# Keyboard40.net
KiCad netlist of a schematic drawn in EAGLE
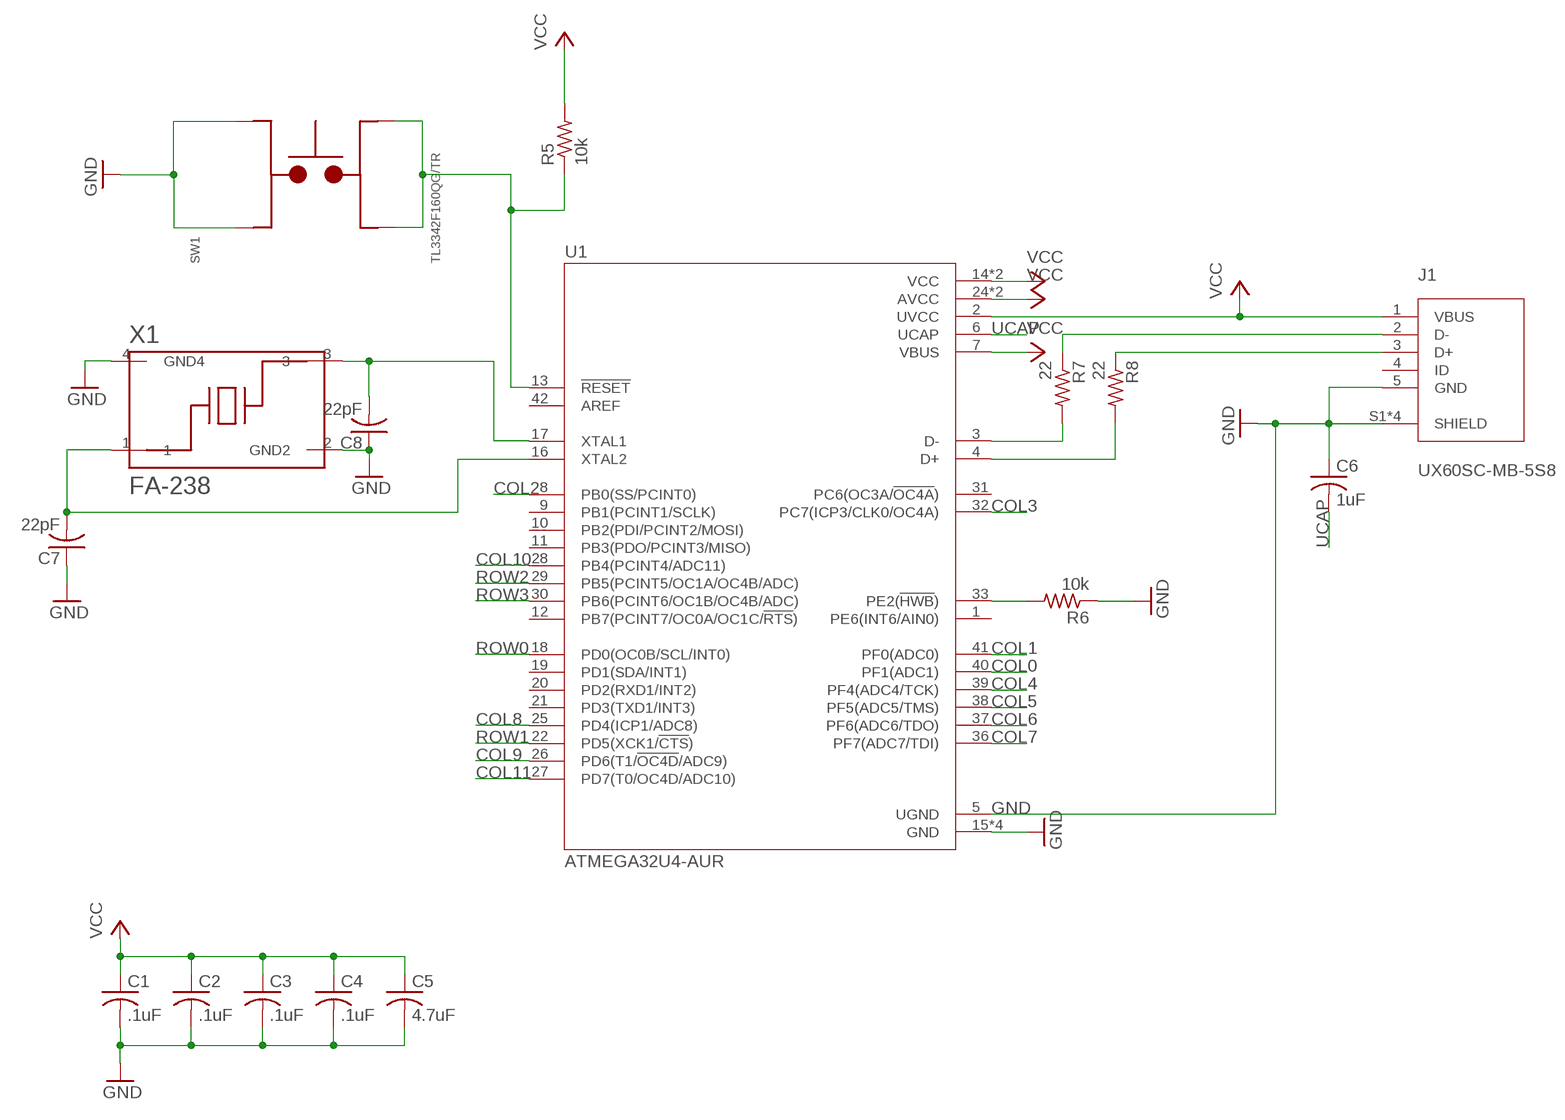
[diagram p0: schematic, sheet 1]
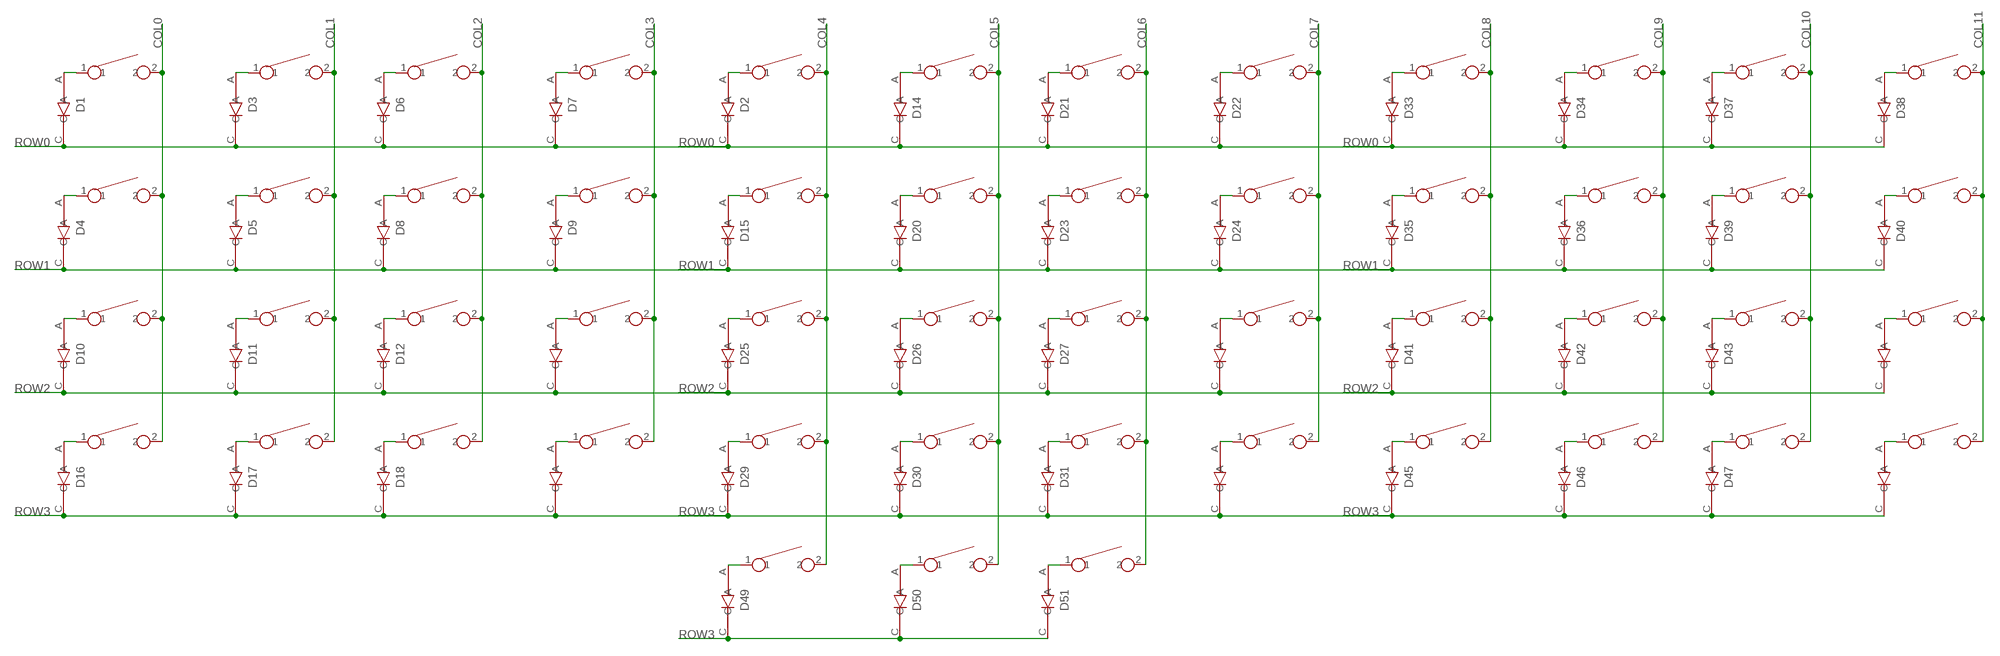
[diagram p1: schematic, sheet 2]

(export (version "E")
  (design (tool "Eeschema 10.0.6"))
  (components
    (comp (ref "D1")
      (value "BAV21W-7-F")
      (footprint "eagle-import:SOD3715X135N")
      (fields (field (name "DIGI-KEY_PART_NUMBER") "BAV21W-FDICT-ND") (field (name "MF") "Diodes Inc."))
      (libsource (lib "eagle-import") (part "BAV21W-7-F"))
    )
    (comp (ref "D2")
      (value "BAV21W-7-F")
      (footprint "eagle-import:SOD3715X135N")
      (fields (field (name "DIGI-KEY_PART_NUMBER") "BAV21W-FDICT-ND") (field (name "MF") "Diodes Inc."))
      (libsource (lib "eagle-import") (part "BAV21W-7-F"))
    )
    (comp (ref "D3")
      (value "BAV21W-7-F")
      (footprint "eagle-import:SOD3715X135N")
      (fields (field (name "DIGI-KEY_PART_NUMBER") "BAV21W-FDICT-ND") (field (name "MF") "Diodes Inc."))
      (libsource (lib "eagle-import") (part "BAV21W-7-F"))
    )
    (comp (ref "D4")
      (value "BAV21W-7-F")
      (footprint "eagle-import:SOD3715X135N")
      (fields (field (name "DIGI-KEY_PART_NUMBER") "BAV21W-FDICT-ND") (field (name "MF") "Diodes Inc."))
      (libsource (lib "eagle-import") (part "BAV21W-7-F"))
    )
    (comp (ref "D5")
      (value "BAV21W-7-F")
      (footprint "eagle-import:SOD3715X135N")
      (fields (field (name "DIGI-KEY_PART_NUMBER") "BAV21W-FDICT-ND") (field (name "MF") "Diodes Inc."))
      (libsource (lib "eagle-import") (part "BAV21W-7-F"))
    )
    (comp (ref "D6")
      (value "BAV21W-7-F")
      (footprint "eagle-import:SOD3715X135N")
      (fields (field (name "DIGI-KEY_PART_NUMBER") "BAV21W-FDICT-ND") (field (name "MF") "Diodes Inc."))
      (libsource (lib "eagle-import") (part "BAV21W-7-F"))
    )
    (comp (ref "D7")
      (value "BAV21W-7-F")
      (footprint "eagle-import:SOD3715X135N")
      (fields (field (name "DIGI-KEY_PART_NUMBER") "BAV21W-FDICT-ND") (field (name "MF") "Diodes Inc."))
      (libsource (lib "eagle-import") (part "BAV21W-7-F"))
    )
    (comp (ref "D8")
      (value "BAV21W-7-F")
      (footprint "eagle-import:SOD3715X135N")
      (fields (field (name "DIGI-KEY_PART_NUMBER") "BAV21W-FDICT-ND") (field (name "MF") "Diodes Inc."))
      (libsource (lib "eagle-import") (part "BAV21W-7-F"))
    )
    (comp (ref "D9")
      (value "BAV21W-7-F")
      (footprint "eagle-import:SOD3715X135N")
      (fields (field (name "DIGI-KEY_PART_NUMBER") "BAV21W-FDICT-ND") (field (name "MF") "Diodes Inc."))
      (libsource (lib "eagle-import") (part "BAV21W-7-F"))
    )
    (comp (ref "D10")
      (value "BAV21W-7-F")
      (footprint "eagle-import:SOD3715X135N")
      (fields (field (name "DIGI-KEY_PART_NUMBER") "BAV21W-FDICT-ND") (field (name "MF") "Diodes Inc."))
      (libsource (lib "eagle-import") (part "BAV21W-7-F"))
    )
    (comp (ref "D11")
      (value "BAV21W-7-F")
      (footprint "eagle-import:SOD3715X135N")
      (fields (field (name "DIGI-KEY_PART_NUMBER") "BAV21W-FDICT-ND") (field (name "MF") "Diodes Inc."))
      (libsource (lib "eagle-import") (part "BAV21W-7-F"))
    )
    (comp (ref "D12")
      (value "BAV21W-7-F")
      (footprint "eagle-import:SOD3715X135N")
      (fields (field (name "DIGI-KEY_PART_NUMBER") "BAV21W-FDICT-ND") (field (name "MF") "Diodes Inc."))
      (libsource (lib "eagle-import") (part "BAV21W-7-F"))
    )
    (comp (ref "D13")
      (value "BAV21W-7-F")
      (footprint "eagle-import:SOD3715X135N")
      (fields (field (name "DIGI-KEY_PART_NUMBER") "BAV21W-FDICT-ND") (field (name "MF") "Diodes Inc."))
      (libsource (lib "eagle-import") (part "BAV21W-7-F"))
    )
    (comp (ref "D14")
      (value "BAV21W-7-F")
      (footprint "eagle-import:SOD3715X135N")
      (fields (field (name "DIGI-KEY_PART_NUMBER") "BAV21W-FDICT-ND") (field (name "MF") "Diodes Inc."))
      (libsource (lib "eagle-import") (part "BAV21W-7-F"))
    )
    (comp (ref "D15")
      (value "BAV21W-7-F")
      (footprint "eagle-import:SOD3715X135N")
      (fields (field (name "DIGI-KEY_PART_NUMBER") "BAV21W-FDICT-ND") (field (name "MF") "Diodes Inc."))
      (libsource (lib "eagle-import") (part "BAV21W-7-F"))
    )
    (comp (ref "D16")
      (value "BAV21W-7-F")
      (footprint "eagle-import:SOD3715X135N")
      (fields (field (name "DIGI-KEY_PART_NUMBER") "BAV21W-FDICT-ND") (field (name "MF") "Diodes Inc."))
      (libsource (lib "eagle-import") (part "BAV21W-7-F"))
    )
    (comp (ref "D17")
      (value "BAV21W-7-F")
      (footprint "eagle-import:SOD3715X135N")
      (fields (field (name "DIGI-KEY_PART_NUMBER") "BAV21W-FDICT-ND") (field (name "MF") "Diodes Inc."))
      (libsource (lib "eagle-import") (part "BAV21W-7-F"))
    )
    (comp (ref "D18")
      (value "BAV21W-7-F")
      (footprint "eagle-import:SOD3715X135N")
      (fields (field (name "DIGI-KEY_PART_NUMBER") "BAV21W-FDICT-ND") (field (name "MF") "Diodes Inc."))
      (libsource (lib "eagle-import") (part "BAV21W-7-F"))
    )
    (comp (ref "D19")
      (value "BAV21W-7-F")
      (footprint "eagle-import:SOD3715X135N")
      (fields (field (name "DIGI-KEY_PART_NUMBER") "BAV21W-FDICT-ND") (field (name "MF") "Diodes Inc."))
      (libsource (lib "eagle-import") (part "BAV21W-7-F"))
    )
    (comp (ref "D20")
      (value "BAV21W-7-F")
      (footprint "eagle-import:SOD3715X135N")
      (fields (field (name "DIGI-KEY_PART_NUMBER") "BAV21W-FDICT-ND") (field (name "MF") "Diodes Inc."))
      (libsource (lib "eagle-import") (part "BAV21W-7-F"))
    )
    (comp (ref "D21")
      (value "BAV21W-7-F")
      (footprint "eagle-import:SOD3715X135N")
      (fields (field (name "DIGI-KEY_PART_NUMBER") "BAV21W-FDICT-ND") (field (name "MF") "Diodes Inc."))
      (libsource (lib "eagle-import") (part "BAV21W-7-F"))
    )
    (comp (ref "D22")
      (value "BAV21W-7-F")
      (footprint "eagle-import:SOD3715X135N")
      (fields (field (name "DIGI-KEY_PART_NUMBER") "BAV21W-FDICT-ND") (field (name "MF") "Diodes Inc."))
      (libsource (lib "eagle-import") (part "BAV21W-7-F"))
    )
    (comp (ref "D23")
      (value "BAV21W-7-F")
      (footprint "eagle-import:SOD3715X135N")
      (fields (field (name "DIGI-KEY_PART_NUMBER") "BAV21W-FDICT-ND") (field (name "MF") "Diodes Inc."))
      (libsource (lib "eagle-import") (part "BAV21W-7-F"))
    )
    (comp (ref "D24")
      (value "BAV21W-7-F")
      (footprint "eagle-import:SOD3715X135N")
      (fields (field (name "DIGI-KEY_PART_NUMBER") "BAV21W-FDICT-ND") (field (name "MF") "Diodes Inc."))
      (libsource (lib "eagle-import") (part "BAV21W-7-F"))
    )
    (comp (ref "D25")
      (value "BAV21W-7-F")
      (footprint "eagle-import:SOD3715X135N")
      (fields (field (name "DIGI-KEY_PART_NUMBER") "BAV21W-FDICT-ND") (field (name "MF") "Diodes Inc."))
      (libsource (lib "eagle-import") (part "BAV21W-7-F"))
    )
    (comp (ref "D26")
      (value "BAV21W-7-F")
      (footprint "eagle-import:SOD3715X135N")
      (fields (field (name "DIGI-KEY_PART_NUMBER") "BAV21W-FDICT-ND") (field (name "MF") "Diodes Inc."))
      (libsource (lib "eagle-import") (part "BAV21W-7-F"))
    )
    (comp (ref "D27")
      (value "BAV21W-7-F")
      (footprint "eagle-import:SOD3715X135N")
      (fields (field (name "DIGI-KEY_PART_NUMBER") "BAV21W-FDICT-ND") (field (name "MF") "Diodes Inc."))
      (libsource (lib "eagle-import") (part "BAV21W-7-F"))
    )
    (comp (ref "D28")
      (value "BAV21W-7-F")
      (footprint "eagle-import:SOD3715X135N")
      (fields (field (name "DIGI-KEY_PART_NUMBER") "BAV21W-FDICT-ND") (field (name "MF") "Diodes Inc."))
      (libsource (lib "eagle-import") (part "BAV21W-7-F"))
    )
    (comp (ref "D29")
      (value "BAV21W-7-F")
      (footprint "eagle-import:SOD3715X135N")
      (fields (field (name "DIGI-KEY_PART_NUMBER") "BAV21W-FDICT-ND") (field (name "MF") "Diodes Inc."))
      (libsource (lib "eagle-import") (part "BAV21W-7-F"))
    )
    (comp (ref "D30")
      (value "BAV21W-7-F")
      (footprint "eagle-import:SOD3715X135N")
      (fields (field (name "DIGI-KEY_PART_NUMBER") "BAV21W-FDICT-ND") (field (name "MF") "Diodes Inc."))
      (libsource (lib "eagle-import") (part "BAV21W-7-F"))
    )
    (comp (ref "D31")
      (value "BAV21W-7-F")
      (footprint "eagle-import:SOD3715X135N")
      (fields (field (name "DIGI-KEY_PART_NUMBER") "BAV21W-FDICT-ND") (field (name "MF") "Diodes Inc."))
      (libsource (lib "eagle-import") (part "BAV21W-7-F"))
    )
    (comp (ref "D32")
      (value "BAV21W-7-F")
      (footprint "eagle-import:SOD3715X135N")
      (fields (field (name "DIGI-KEY_PART_NUMBER") "BAV21W-FDICT-ND") (field (name "MF") "Diodes Inc."))
      (libsource (lib "eagle-import") (part "BAV21W-7-F"))
    )
    (comp (ref "D33")
      (value "BAV21W-7-F")
      (footprint "eagle-import:SOD3715X135N")
      (fields (field (name "DIGI-KEY_PART_NUMBER") "BAV21W-FDICT-ND") (field (name "MF") "Diodes Inc."))
      (libsource (lib "eagle-import") (part "BAV21W-7-F"))
    )
    (comp (ref "D34")
      (value "BAV21W-7-F")
      (footprint "eagle-import:SOD3715X135N")
      (fields (field (name "DIGI-KEY_PART_NUMBER") "BAV21W-FDICT-ND") (field (name "MF") "Diodes Inc."))
      (libsource (lib "eagle-import") (part "BAV21W-7-F"))
    )
    (comp (ref "D35")
      (value "BAV21W-7-F")
      (footprint "eagle-import:SOD3715X135N")
      (fields (field (name "DIGI-KEY_PART_NUMBER") "BAV21W-FDICT-ND") (field (name "MF") "Diodes Inc."))
      (libsource (lib "eagle-import") (part "BAV21W-7-F"))
    )
    (comp (ref "D36")
      (value "BAV21W-7-F")
      (footprint "eagle-import:SOD3715X135N")
      (fields (field (name "DIGI-KEY_PART_NUMBER") "BAV21W-FDICT-ND") (field (name "MF") "Diodes Inc."))
      (libsource (lib "eagle-import") (part "BAV21W-7-F"))
    )
    (comp (ref "D37")
      (value "BAV21W-7-F")
      (footprint "eagle-import:SOD3715X135N")
      (fields (field (name "DIGI-KEY_PART_NUMBER") "BAV21W-FDICT-ND") (field (name "MF") "Diodes Inc."))
      (libsource (lib "eagle-import") (part "BAV21W-7-F"))
    )
    (comp (ref "D38")
      (value "BAV21W-7-F")
      (footprint "eagle-import:SOD3715X135N")
      (fields (field (name "DIGI-KEY_PART_NUMBER") "BAV21W-FDICT-ND") (field (name "MF") "Diodes Inc."))
      (libsource (lib "eagle-import") (part "BAV21W-7-F"))
    )
    (comp (ref "D39")
      (value "BAV21W-7-F")
      (footprint "eagle-import:SOD3715X135N")
      (fields (field (name "DIGI-KEY_PART_NUMBER") "BAV21W-FDICT-ND") (field (name "MF") "Diodes Inc."))
      (libsource (lib "eagle-import") (part "BAV21W-7-F"))
    )
    (comp (ref "D40")
      (value "BAV21W-7-F")
      (footprint "eagle-import:SOD3715X135N")
      (fields (field (name "DIGI-KEY_PART_NUMBER") "BAV21W-FDICT-ND") (field (name "MF") "Diodes Inc."))
      (libsource (lib "eagle-import") (part "BAV21W-7-F"))
    )
    (comp (ref "D41")
      (value "BAV21W-7-F")
      (footprint "eagle-import:SOD3715X135N")
      (fields (field (name "DIGI-KEY_PART_NUMBER") "BAV21W-FDICT-ND") (field (name "MF") "Diodes Inc."))
      (libsource (lib "eagle-import") (part "BAV21W-7-F"))
    )
    (comp (ref "D42")
      (value "BAV21W-7-F")
      (footprint "eagle-import:SOD3715X135N")
      (fields (field (name "DIGI-KEY_PART_NUMBER") "BAV21W-FDICT-ND") (field (name "MF") "Diodes Inc."))
      (libsource (lib "eagle-import") (part "BAV21W-7-F"))
    )
    (comp (ref "D43")
      (value "BAV21W-7-F")
      (footprint "eagle-import:SOD3715X135N")
      (fields (field (name "DIGI-KEY_PART_NUMBER") "BAV21W-FDICT-ND") (field (name "MF") "Diodes Inc."))
      (libsource (lib "eagle-import") (part "BAV21W-7-F"))
    )
    (comp (ref "D44")
      (value "BAV21W-7-F")
      (footprint "eagle-import:SOD3715X135N")
      (fields (field (name "DIGI-KEY_PART_NUMBER") "BAV21W-FDICT-ND") (field (name "MF") "Diodes Inc."))
      (libsource (lib "eagle-import") (part "BAV21W-7-F"))
    )
    (comp (ref "D45")
      (value "BAV21W-7-F")
      (footprint "eagle-import:SOD3715X135N")
      (fields (field (name "DIGI-KEY_PART_NUMBER") "BAV21W-FDICT-ND") (field (name "MF") "Diodes Inc."))
      (libsource (lib "eagle-import") (part "BAV21W-7-F"))
    )
    (comp (ref "D46")
      (value "BAV21W-7-F")
      (footprint "eagle-import:SOD3715X135N")
      (fields (field (name "DIGI-KEY_PART_NUMBER") "BAV21W-FDICT-ND") (field (name "MF") "Diodes Inc."))
      (libsource (lib "eagle-import") (part "BAV21W-7-F"))
    )
    (comp (ref "D47")
      (value "BAV21W-7-F")
      (footprint "eagle-import:SOD3715X135N")
      (fields (field (name "DIGI-KEY_PART_NUMBER") "BAV21W-FDICT-ND") (field (name "MF") "Diodes Inc."))
      (libsource (lib "eagle-import") (part "BAV21W-7-F"))
    )
    (comp (ref "D48")
      (value "BAV21W-7-F")
      (footprint "eagle-import:SOD3715X135N")
      (fields (field (name "DIGI-KEY_PART_NUMBER") "BAV21W-FDICT-ND") (field (name "MF") "Diodes Inc."))
      (libsource (lib "eagle-import") (part "BAV21W-7-F"))
    )
    (comp (ref "D49")
      (value "BAV21W-7-F")
      (footprint "eagle-import:SOD3715X135N")
      (fields (field (name "DIGI-KEY_PART_NUMBER") "BAV21W-FDICT-ND") (field (name "MF") "Diodes Inc."))
      (libsource (lib "eagle-import") (part "BAV21W-7-F"))
    )
    (comp (ref "D50")
      (value "BAV21W-7-F")
      (footprint "eagle-import:SOD3715X135N")
      (fields (field (name "DIGI-KEY_PART_NUMBER") "BAV21W-FDICT-ND") (field (name "MF") "Diodes Inc."))
      (libsource (lib "eagle-import") (part "BAV21W-7-F"))
    )
    (comp (ref "D51")
      (value "BAV21W-7-F")
      (footprint "eagle-import:SOD3715X135N")
      (fields (field (name "DIGI-KEY_PART_NUMBER") "BAV21W-FDICT-ND") (field (name "MF") "Diodes Inc."))
      (libsource (lib "eagle-import") (part "BAV21W-7-F"))
    )
    (comp (ref "U$1")
      (value "CHERRY_MXCHERRY_MX_PLATE")
      (footprint "eagle-import:CHERRY_MX_PLATE")
      (libsource (lib "eagle-import") (part "CHERRY_MXCHERRY_MX_PLATE"))
    )
    (comp (ref "U$2")
      (value "CHERRY_MXCHERRY_MX_PLATE")
      (footprint "eagle-import:CHERRY_MX_PLATE")
      (libsource (lib "eagle-import") (part "CHERRY_MXCHERRY_MX_PLATE"))
    )
    (comp (ref "U$3")
      (value "CHERRY_MXCHERRY_MX_PLATE")
      (footprint "eagle-import:CHERRY_MX_PLATE")
      (libsource (lib "eagle-import") (part "CHERRY_MXCHERRY_MX_PLATE"))
    )
    (comp (ref "U$4")
      (value "CHERRY_MXCHERRY_MX_PLATE")
      (footprint "eagle-import:CHERRY_MX_PLATE")
      (libsource (lib "eagle-import") (part "CHERRY_MXCHERRY_MX_PLATE"))
    )
    (comp (ref "U$5")
      (value "CHERRY_MXCHERRY_MX_PLATE")
      (footprint "eagle-import:CHERRY_MX_PLATE")
      (libsource (lib "eagle-import") (part "CHERRY_MXCHERRY_MX_PLATE"))
    )
    (comp (ref "U$6")
      (value "CHERRY_MXCHERRY_MX_PLATE")
      (footprint "eagle-import:CHERRY_MX_PLATE")
      (libsource (lib "eagle-import") (part "CHERRY_MXCHERRY_MX_PLATE"))
    )
    (comp (ref "U$7")
      (value "CHERRY_MXCHERRY_MX_PLATE")
      (footprint "eagle-import:CHERRY_MX_PLATE")
      (libsource (lib "eagle-import") (part "CHERRY_MXCHERRY_MX_PLATE"))
    )
    (comp (ref "U$8")
      (value "CHERRY_MXCHERRY_MX_PLATE")
      (footprint "eagle-import:CHERRY_MX_PLATE")
      (libsource (lib "eagle-import") (part "CHERRY_MXCHERRY_MX_PLATE"))
    )
    (comp (ref "U$9")
      (value "CHERRY_MXCHERRY_MX_PLATE")
      (footprint "eagle-import:CHERRY_MX_PLATE")
      (libsource (lib "eagle-import") (part "CHERRY_MXCHERRY_MX_PLATE"))
    )
    (comp (ref "U$10")
      (value "CHERRY_MXCHERRY_MX_PLATE")
      (footprint "eagle-import:CHERRY_MX_PLATE")
      (libsource (lib "eagle-import") (part "CHERRY_MXCHERRY_MX_PLATE"))
    )
    (comp (ref "U$11")
      (value "CHERRY_MXCHERRY_MX_PLATE")
      (footprint "eagle-import:CHERRY_MX_PLATE")
      (libsource (lib "eagle-import") (part "CHERRY_MXCHERRY_MX_PLATE"))
    )
    (comp (ref "U$12")
      (value "CHERRY_MXCHERRY_MX_PLATE")
      (footprint "eagle-import:CHERRY_MX_PLATE")
      (libsource (lib "eagle-import") (part "CHERRY_MXCHERRY_MX_PLATE"))
    )
    (comp (ref "U$13")
      (value "CHERRY_MXCHERRY_MX_1_2_PLATE")
      (footprint "eagle-import:CHERRY_MX_1_2_PLATE")
      (libsource (lib "eagle-import") (part "CHERRY_MXCHERRY_MX_1_2_PLATE"))
    )
    (comp (ref "U$14")
      (value "CHERRY_MXCHERRY_MX_1_2_PLATE")
      (footprint "eagle-import:CHERRY_MX_1_2_PLATE")
      (libsource (lib "eagle-import") (part "CHERRY_MXCHERRY_MX_1_2_PLATE"))
    )
    (comp (ref "U$15")
      (value "CHERRY_MXCHERRY_MX_1_2_PLATE")
      (footprint "eagle-import:CHERRY_MX_1_2_PLATE")
      (libsource (lib "eagle-import") (part "CHERRY_MXCHERRY_MX_1_2_PLATE"))
    )
    (comp (ref "U$16")
      (value "CHERRY_MXCHERRY_MX_PLATE")
      (footprint "eagle-import:CHERRY_MX_PLATE")
      (libsource (lib "eagle-import") (part "CHERRY_MXCHERRY_MX_PLATE"))
    )
    (comp (ref "U$17")
      (value "CHERRY_MXCHERRY_MX_PLATE")
      (footprint "eagle-import:CHERRY_MX_PLATE")
      (libsource (lib "eagle-import") (part "CHERRY_MXCHERRY_MX_PLATE"))
    )
    (comp (ref "U$18")
      (value "CHERRY_MXCHERRY_MX_PLATE")
      (footprint "eagle-import:CHERRY_MX_PLATE")
      (libsource (lib "eagle-import") (part "CHERRY_MXCHERRY_MX_PLATE"))
    )
    (comp (ref "U$19")
      (value "CHERRY_MXCHERRY_MX_PLATE")
      (footprint "eagle-import:CHERRY_MX_PLATE")
      (libsource (lib "eagle-import") (part "CHERRY_MXCHERRY_MX_PLATE"))
    )
    (comp (ref "U$20")
      (value "CHERRY_MXCHERRY_MX_PLATE")
      (footprint "eagle-import:CHERRY_MX_PLATE")
      (libsource (lib "eagle-import") (part "CHERRY_MXCHERRY_MX_PLATE"))
    )
    (comp (ref "U$21")
      (value "CHERRY_MXCHERRY_MX_PLATE")
      (footprint "eagle-import:CHERRY_MX_PLATE")
      (libsource (lib "eagle-import") (part "CHERRY_MXCHERRY_MX_PLATE"))
    )
    (comp (ref "U$22")
      (value "CHERRY_MXCHERRY_MX_PLATE")
      (footprint "eagle-import:CHERRY_MX_PLATE")
      (libsource (lib "eagle-import") (part "CHERRY_MXCHERRY_MX_PLATE"))
    )
    (comp (ref "U$23")
      (value "CHERRY_MXCHERRY_MX_PLATE")
      (footprint "eagle-import:CHERRY_MX_PLATE")
      (libsource (lib "eagle-import") (part "CHERRY_MXCHERRY_MX_PLATE"))
    )
    (comp (ref "U$24")
      (value "CHERRY_MXCHERRY_MX_PLATE")
      (footprint "eagle-import:CHERRY_MX_PLATE")
      (libsource (lib "eagle-import") (part "CHERRY_MXCHERRY_MX_PLATE"))
    )
    (comp (ref "U$25")
      (value "CHERRY_MXCHERRY_MX_PLATE")
      (footprint "eagle-import:CHERRY_MX_PLATE")
      (libsource (lib "eagle-import") (part "CHERRY_MXCHERRY_MX_PLATE"))
    )
    (comp (ref "U$26")
      (value "CHERRY_MXCHERRY_MX_PLATE")
      (footprint "eagle-import:CHERRY_MX_PLATE")
      (libsource (lib "eagle-import") (part "CHERRY_MXCHERRY_MX_PLATE"))
    )
    (comp (ref "U$27")
      (value "CHERRY_MXCHERRY_MX_PLATE")
      (footprint "eagle-import:CHERRY_MX_PLATE")
      (libsource (lib "eagle-import") (part "CHERRY_MXCHERRY_MX_PLATE"))
    )
    (comp (ref "U$28")
      (value "CHERRY_MXCHERRY_MX_PLATE")
      (footprint "eagle-import:CHERRY_MX_PLATE")
      (libsource (lib "eagle-import") (part "CHERRY_MXCHERRY_MX_PLATE"))
    )
    (comp (ref "U$29")
      (value "CHERRY_MXCHERRY_MX_PLATE")
      (footprint "eagle-import:CHERRY_MX_PLATE")
      (libsource (lib "eagle-import") (part "CHERRY_MXCHERRY_MX_PLATE"))
    )
    (comp (ref "U$30")
      (value "CHERRY_MXCHERRY_MX_PLATE")
      (footprint "eagle-import:CHERRY_MX_PLATE")
      (libsource (lib "eagle-import") (part "CHERRY_MXCHERRY_MX_PLATE"))
    )
    (comp (ref "U$31")
      (value "CHERRY_MXCHERRY_MX_PLATE")
      (footprint "eagle-import:CHERRY_MX_PLATE")
      (libsource (lib "eagle-import") (part "CHERRY_MXCHERRY_MX_PLATE"))
    )
    (comp (ref "U$32")
      (value "CHERRY_MXCHERRY_MX_PLATE")
      (footprint "eagle-import:CHERRY_MX_PLATE")
      (libsource (lib "eagle-import") (part "CHERRY_MXCHERRY_MX_PLATE"))
    )
    (comp (ref "U$33")
      (value "CHERRY_MXCHERRY_MX_PLATE")
      (footprint "eagle-import:CHERRY_MX_PLATE")
      (libsource (lib "eagle-import") (part "CHERRY_MXCHERRY_MX_PLATE"))
    )
    (comp (ref "U$34")
      (value "CHERRY_MXCHERRY_MX_PLATE")
      (footprint "eagle-import:CHERRY_MX_PLATE")
      (libsource (lib "eagle-import") (part "CHERRY_MXCHERRY_MX_PLATE"))
    )
    (comp (ref "U$35")
      (value "CHERRY_MXCHERRY_MX_PLATE")
      (footprint "eagle-import:CHERRY_MX_PLATE")
      (libsource (lib "eagle-import") (part "CHERRY_MXCHERRY_MX_PLATE"))
    )
    (comp (ref "U$36")
      (value "CHERRY_MXCHERRY_MX_PLATE")
      (footprint "eagle-import:CHERRY_MX_PLATE")
      (libsource (lib "eagle-import") (part "CHERRY_MXCHERRY_MX_PLATE"))
    )
    (comp (ref "U$37")
      (value "CHERRY_MXCHERRY_MX_PLATE")
      (footprint "eagle-import:CHERRY_MX_PLATE")
      (libsource (lib "eagle-import") (part "CHERRY_MXCHERRY_MX_PLATE"))
    )
    (comp (ref "U$38")
      (value "CHERRY_MXCHERRY_MX_PLATE")
      (footprint "eagle-import:CHERRY_MX_PLATE")
      (libsource (lib "eagle-import") (part "CHERRY_MXCHERRY_MX_PLATE"))
    )
    (comp (ref "U$39")
      (value "CHERRY_MXCHERRY_MX_PLATE")
      (footprint "eagle-import:CHERRY_MX_PLATE")
      (libsource (lib "eagle-import") (part "CHERRY_MXCHERRY_MX_PLATE"))
    )
    (comp (ref "U$40")
      (value "CHERRY_MXCHERRY_MX_PLATE")
      (footprint "eagle-import:CHERRY_MX_PLATE")
      (libsource (lib "eagle-import") (part "CHERRY_MXCHERRY_MX_PLATE"))
    )
    (comp (ref "U$41")
      (value "CHERRY_MXCHERRY_MX_PLATE")
      (footprint "eagle-import:CHERRY_MX_PLATE")
      (libsource (lib "eagle-import") (part "CHERRY_MXCHERRY_MX_PLATE"))
    )
    (comp (ref "U$42")
      (value "CHERRY_MXCHERRY_MX_PLATE")
      (footprint "eagle-import:CHERRY_MX_PLATE")
      (libsource (lib "eagle-import") (part "CHERRY_MXCHERRY_MX_PLATE"))
    )
    (comp (ref "U$43")
      (value "CHERRY_MXCHERRY_MX_PLATE")
      (footprint "eagle-import:CHERRY_MX_PLATE")
      (libsource (lib "eagle-import") (part "CHERRY_MXCHERRY_MX_PLATE"))
    )
    (comp (ref "U$44")
      (value "CHERRY_MXCHERRY_MX_PLATE")
      (footprint "eagle-import:CHERRY_MX_PLATE")
      (libsource (lib "eagle-import") (part "CHERRY_MXCHERRY_MX_PLATE"))
    )
    (comp (ref "U$45")
      (value "CHERRY_MXCHERRY_MX_PLATE")
      (footprint "eagle-import:CHERRY_MX_PLATE")
      (libsource (lib "eagle-import") (part "CHERRY_MXCHERRY_MX_PLATE"))
    )
    (comp (ref "U$46")
      (value "CHERRY_MXCHERRY_MX_PLATE")
      (footprint "eagle-import:CHERRY_MX_PLATE")
      (libsource (lib "eagle-import") (part "CHERRY_MXCHERRY_MX_PLATE"))
    )
    (comp (ref "U$47")
      (value "CHERRY_MXCHERRY_MX_PLATE")
      (footprint "eagle-import:CHERRY_MX_PLATE")
      (libsource (lib "eagle-import") (part "CHERRY_MXCHERRY_MX_PLATE"))
    )
    (comp (ref "U$48")
      (value "CHERRY_MXCHERRY_MX_PLATE")
      (footprint "eagle-import:CHERRY_MX_PLATE")
      (libsource (lib "eagle-import") (part "CHERRY_MXCHERRY_MX_PLATE"))
    )
    (comp (ref "U$49")
      (value "CHERRY_MXCHERRY_MX_PLATE")
      (footprint "eagle-import:CHERRY_MX_PLATE")
      (libsource (lib "eagle-import") (part "CHERRY_MXCHERRY_MX_PLATE"))
    )
    (comp (ref "U$50")
      (value "CHERRY_MXCHERRY_MX_PLATE")
      (footprint "eagle-import:CHERRY_MX_PLATE")
      (libsource (lib "eagle-import") (part "CHERRY_MXCHERRY_MX_PLATE"))
    )
    (comp (ref "U$51")
      (value "CHERRY_MXCHERRY_MX_PLATE")
      (footprint "eagle-import:CHERRY_MX_PLATE")
      (libsource (lib "eagle-import") (part "CHERRY_MXCHERRY_MX_PLATE"))
    )
    (comp (ref "C1")
      (value ".1uF")
      (footprint "eagle-import:C0805")
      (libsource (lib "eagle-import") (part "C-USC0805"))
    )
    (comp (ref "C2")
      (value ".1uF")
      (footprint "eagle-import:C0805")
      (libsource (lib "eagle-import") (part "C-USC0805"))
    )
    (comp (ref "C3")
      (value ".1uF")
      (footprint "eagle-import:C0805")
      (libsource (lib "eagle-import") (part "C-USC0805"))
    )
    (comp (ref "C4")
      (value ".1uF")
      (footprint "eagle-import:C0805")
      (libsource (lib "eagle-import") (part "C-USC0805"))
    )
    (comp (ref "C5")
      (value "4.7uF")
      (footprint "eagle-import:C0805")
      (libsource (lib "eagle-import") (part "C-USC0805"))
    )
    (comp (ref "C6")
      (value "1uF")
      (footprint "eagle-import:C0805")
      (libsource (lib "eagle-import") (part "C-USC0805"))
    )
    (comp (ref "C7")
      (value "22pF")
      (footprint "eagle-import:C0805")
      (libsource (lib "eagle-import") (part "C-USC0805"))
    )
    (comp (ref "C8")
      (value "22pF")
      (footprint "eagle-import:C0805")
      (libsource (lib "eagle-import") (part "C-USC0805"))
    )
    (comp (ref "J1")
      (value "UX60SC-MB-5S8")
      (footprint "eagle-import:HIROSE_UX60SC-MB-5S8")
      (fields (field (name "MF") "Hirose"))
      (libsource (lib "eagle-import") (part "UX60SC-MB-5S8"))
    )
    (comp (ref "R5")
      (value "10k")
      (footprint "eagle-import:R0805")
      (libsource (lib "eagle-import") (part "R-US_R0805"))
    )
    (comp (ref "R6")
      (value "10k")
      (footprint "eagle-import:R0805")
      (libsource (lib "eagle-import") (part "R-US_R0805"))
    )
    (comp (ref "R7")
      (value "22")
      (footprint "eagle-import:R0805")
      (libsource (lib "eagle-import") (part "R-US_R0805"))
    )
    (comp (ref "R8")
      (value "22")
      (footprint "eagle-import:R0805")
      (libsource (lib "eagle-import") (part "R-US_R0805"))
    )
    (comp (ref "SW1")
      (value "TL3342F160QG/TR")
      (footprint "eagle-import:SW_TL3342F160QG_TR")
      (fields (field (name "MF") "E-Switch"))
      (libsource (lib "eagle-import") (part "TL3342F160QG/TR"))
    )
    (comp (ref "U1")
      (value "ATMEGA32U4-AUR")
      (footprint "eagle-import:QFP80P1200X1200X120-44N")
      (fields (field (name "MF") "Microchip"))
      (libsource (lib "eagle-import") (part "ATMEGA32U4-AUR"))
    )
    (comp (ref "X1")
      (value "FA-238")
      (footprint "eagle-import:OSCCC320X250X70-4N")
      (fields (field (name "MF") "EPSON"))
      (libsource (lib "eagle-import") (part "FA-238"))
    )
  )
  (nets
    (net (code "1") (name "COL0") (class "Default")
      (node (ref "U$1") (pin "2") (pinfunction "2_2") (pintype "bidirectional"))
      (node (ref "U$17") (pin "2") (pinfunction "2_2") (pintype "bidirectional"))
      (node (ref "U$2") (pin "2") (pinfunction "2_2") (pintype "bidirectional"))
      (node (ref "U$3") (pin "2") (pinfunction "2_2") (pintype "bidirectional"))
      (node (ref "U1") (pin "40") (pinfunction "PF1(ADC1)_40") (pintype "bidirectional"))
    )
    (net (code "2") (name "COL1") (class "Default")
      (node (ref "U$18") (pin "2") (pinfunction "2_2") (pintype "bidirectional"))
      (node (ref "U$4") (pin "2") (pinfunction "2_2") (pintype "bidirectional"))
      (node (ref "U$5") (pin "2") (pinfunction "2_2") (pintype "bidirectional"))
      (node (ref "U$6") (pin "2") (pinfunction "2_2") (pintype "bidirectional"))
      (node (ref "U1") (pin "41") (pinfunction "PF0(ADC0)_41") (pintype "bidirectional"))
    )
    (net (code "3") (name "COL2") (class "Default")
      (node (ref "U$19") (pin "2") (pinfunction "2_2") (pintype "bidirectional"))
      (node (ref "U$7") (pin "2") (pinfunction "2_2") (pintype "bidirectional"))
      (node (ref "U$8") (pin "2") (pinfunction "2_2") (pintype "bidirectional"))
      (node (ref "U$9") (pin "2") (pinfunction "2_2") (pintype "bidirectional"))
      (node (ref "U1") (pin "8") (pinfunction "PB0(SS/PCINT0)_8") (pintype "bidirectional"))
    )
    (net (code "4") (name "COL3") (class "Default")
      (node (ref "U$10") (pin "2") (pinfunction "2_2") (pintype "bidirectional"))
      (node (ref "U$11") (pin "2") (pinfunction "2_2") (pintype "bidirectional"))
      (node (ref "U$12") (pin "2") (pinfunction "2_2") (pintype "bidirectional"))
      (node (ref "U$16") (pin "2") (pinfunction "2_2") (pintype "bidirectional"))
      (node (ref "U1") (pin "32") (pinfunction "PC7(ICP3/CLK0/OC4A)_32") (pintype "bidirectional"))
    )
    (net (code "5") (name "COL4") (class "Default")
      (node (ref "U$13") (pin "2") (pinfunction "2_2") (pintype "bidirectional"))
      (node (ref "U$22") (pin "2") (pinfunction "2_2") (pintype "bidirectional"))
      (node (ref "U$23") (pin "2") (pinfunction "2_2") (pintype "bidirectional"))
      (node (ref "U$24") (pin "2") (pinfunction "2_2") (pintype "bidirectional"))
      (node (ref "U$36") (pin "2") (pinfunction "2_2") (pintype "bidirectional"))
      (node (ref "U1") (pin "39") (pinfunction "PF4(ADC4/TCK)_39") (pintype "bidirectional"))
    )
    (net (code "6") (name "COL5") (class "Default")
      (node (ref "U$14") (pin "2") (pinfunction "2_2") (pintype "bidirectional"))
      (node (ref "U$25") (pin "2") (pinfunction "2_2") (pintype "bidirectional"))
      (node (ref "U$26") (pin "2") (pinfunction "2_2") (pintype "bidirectional"))
      (node (ref "U$27") (pin "2") (pinfunction "2_2") (pintype "bidirectional"))
      (node (ref "U$37") (pin "2") (pinfunction "2_2") (pintype "bidirectional"))
      (node (ref "U1") (pin "38") (pinfunction "PF5(ADC5/TMS)_38") (pintype "bidirectional"))
    )
    (net (code "7") (name "COL6") (class "Default")
      (node (ref "U$15") (pin "2") (pinfunction "2_2") (pintype "bidirectional"))
      (node (ref "U$28") (pin "2") (pinfunction "2_2") (pintype "bidirectional"))
      (node (ref "U$29") (pin "2") (pinfunction "2_2") (pintype "bidirectional"))
      (node (ref "U$30") (pin "2") (pinfunction "2_2") (pintype "bidirectional"))
      (node (ref "U$38") (pin "2") (pinfunction "2_2") (pintype "bidirectional"))
      (node (ref "U1") (pin "37") (pinfunction "PF6(ADC6/TDO)_37") (pintype "bidirectional"))
    )
    (net (code "8") (name "COL7") (class "Default")
      (node (ref "U$20") (pin "2") (pinfunction "2_2") (pintype "bidirectional"))
      (node (ref "U$21") (pin "2") (pinfunction "2_2") (pintype "bidirectional"))
      (node (ref "U$31") (pin "2") (pinfunction "2_2") (pintype "bidirectional"))
      (node (ref "U$35") (pin "2") (pinfunction "2_2") (pintype "bidirectional"))
      (node (ref "U1") (pin "36") (pinfunction "PF7(ADC7/TDI)_36") (pintype "bidirectional"))
    )
    (net (code "9") (name "COL8") (class "Default")
      (node (ref "U$34") (pin "2") (pinfunction "2_2") (pintype "bidirectional"))
      (node (ref "U$39") (pin "2") (pinfunction "2_2") (pintype "bidirectional"))
      (node (ref "U$40") (pin "2") (pinfunction "2_2") (pintype "bidirectional"))
      (node (ref "U$49") (pin "2") (pinfunction "2_2") (pintype "bidirectional"))
      (node (ref "U1") (pin "25") (pinfunction "PD4(ICP1/ADC8)_25") (pintype "bidirectional"))
    )
    (net (code "10") (name "COL9") (class "Default")
      (node (ref "U$41") (pin "2") (pinfunction "2_2") (pintype "bidirectional"))
      (node (ref "U$42") (pin "2") (pinfunction "2_2") (pintype "bidirectional"))
      (node (ref "U$43") (pin "2") (pinfunction "2_2") (pintype "bidirectional"))
      (node (ref "U$50") (pin "2") (pinfunction "2_2") (pintype "bidirectional"))
      (node (ref "U1") (pin "26") (pinfunction "PD6(T1/~{OC4D}/ADC9)_26") (pintype "bidirectional"))
    )
    (net (code "11") (name "COL10") (class "Default")
      (node (ref "U$44") (pin "2") (pinfunction "2_2") (pintype "bidirectional"))
      (node (ref "U$45") (pin "2") (pinfunction "2_2") (pintype "bidirectional"))
      (node (ref "U$46") (pin "2") (pinfunction "2_2") (pintype "bidirectional"))
      (node (ref "U$51") (pin "2") (pinfunction "2_2") (pintype "bidirectional"))
      (node (ref "U1") (pin "28") (pinfunction "PB4(PCINT4/ADC11)_28") (pintype "bidirectional"))
    )
    (net (code "12") (name "COL11") (class "Default")
      (node (ref "U$32") (pin "2") (pinfunction "2_2") (pintype "bidirectional"))
      (node (ref "U$33") (pin "2") (pinfunction "2_2") (pintype "bidirectional"))
      (node (ref "U$47") (pin "2") (pinfunction "2_2") (pintype "bidirectional"))
      (node (ref "U$48") (pin "2") (pinfunction "2_2") (pintype "bidirectional"))
      (node (ref "U1") (pin "27") (pinfunction "PD7(T0/OC4D/ADC10)_27") (pintype "bidirectional"))
    )
    (net (code "13") (name "GND") (class "Default")
      (node (ref "C1") (pin "2") (pinfunction "2_2") (pintype "passive"))
      (node (ref "C2") (pin "2") (pinfunction "2_2") (pintype "passive"))
      (node (ref "C3") (pin "2") (pinfunction "2_2") (pintype "passive"))
      (node (ref "C4") (pin "2") (pinfunction "2_2") (pintype "passive"))
      (node (ref "C5") (pin "2") (pinfunction "2_2") (pintype "passive"))
      (node (ref "C6") (pin "1") (pinfunction "1_1") (pintype "passive"))
      (node (ref "C7") (pin "1") (pinfunction "1_1") (pintype "passive"))
      (node (ref "C8") (pin "1") (pinfunction "1_1") (pintype "passive"))
      (node (ref "J1") (pin "5") (pinfunction "GND_5") (pintype "power_in"))
      (node (ref "J1") (pin "S1") (pinfunction "SHIELD_S1") (pintype "power_in"))
      (node (ref "J1") (pin "S2") (pinfunction "SHIELD_S2") (pintype "power_in"))
      (node (ref "J1") (pin "S3") (pinfunction "SHIELD_S3") (pintype "power_in"))
      (node (ref "J1") (pin "S4") (pinfunction "SHIELD_S4") (pintype "power_in"))
      (node (ref "R6") (pin "1") (pinfunction "1_1") (pintype "passive"))
      (node (ref "SW1") (pin "3") (pinfunction "3_3") (pintype "passive"))
      (node (ref "SW1") (pin "4") (pinfunction "4_4") (pintype "passive"))
      (node (ref "U1") (pin "15") (pinfunction "GND_15") (pintype "power_in"))
      (node (ref "U1") (pin "23") (pinfunction "GND_23") (pintype "power_in"))
      (node (ref "U1") (pin "35") (pinfunction "GND_35") (pintype "power_in"))
      (node (ref "U1") (pin "43") (pinfunction "GND_43") (pintype "power_in"))
      (node (ref "U1") (pin "5") (pinfunction "UGND_5") (pintype "power_in"))
      (node (ref "X1") (pin "2") (pinfunction "GND2_2") (pintype "passive"))
      (node (ref "X1") (pin "4") (pinfunction "GND4_4") (pintype "passive"))
    )
    (net (code "14") (name "Net-(D1-PadA)") (class "Default")
      (node (ref "D1") (pin "A") (pinfunction "A_A") (pintype "passive"))
      (node (ref "U$1") (pin "1") (pinfunction "1_1") (pintype "bidirectional"))
    )
    (net (code "15") (name "Net-(D2-PadA)") (class "Default")
      (node (ref "D2") (pin "A") (pinfunction "A_A") (pintype "passive"))
      (node (ref "U$22") (pin "1") (pinfunction "1_1") (pintype "bidirectional"))
    )
    (net (code "16") (name "Net-(D3-PadA)") (class "Default")
      (node (ref "D3") (pin "A") (pinfunction "A_A") (pintype "passive"))
      (node (ref "U$4") (pin "1") (pinfunction "1_1") (pintype "bidirectional"))
    )
    (net (code "17") (name "Net-(D4-PadA)") (class "Default")
      (node (ref "D4") (pin "A") (pinfunction "A_A") (pintype "passive"))
      (node (ref "U$2") (pin "1") (pinfunction "1_1") (pintype "bidirectional"))
    )
    (net (code "18") (name "Net-(D5-PadA)") (class "Default")
      (node (ref "D5") (pin "A") (pinfunction "A_A") (pintype "passive"))
      (node (ref "U$5") (pin "1") (pinfunction "1_1") (pintype "bidirectional"))
    )
    (net (code "19") (name "Net-(D6-PadA)") (class "Default")
      (node (ref "D6") (pin "A") (pinfunction "A_A") (pintype "passive"))
      (node (ref "U$7") (pin "1") (pinfunction "1_1") (pintype "bidirectional"))
    )
    (net (code "20") (name "Net-(D7-PadA)") (class "Default")
      (node (ref "D7") (pin "A") (pinfunction "A_A") (pintype "passive"))
      (node (ref "U$12") (pin "1") (pinfunction "1_1") (pintype "bidirectional"))
    )
    (net (code "21") (name "Net-(D8-PadA)") (class "Default")
      (node (ref "D8") (pin "A") (pinfunction "A_A") (pintype "passive"))
      (node (ref "U$8") (pin "1") (pinfunction "1_1") (pintype "bidirectional"))
    )
    (net (code "22") (name "Net-(D9-PadA)") (class "Default")
      (node (ref "D9") (pin "A") (pinfunction "A_A") (pintype "passive"))
      (node (ref "U$10") (pin "1") (pinfunction "1_1") (pintype "bidirectional"))
    )
    (net (code "23") (name "Net-(D10-PadA)") (class "Default")
      (node (ref "D10") (pin "A") (pinfunction "A_A") (pintype "passive"))
      (node (ref "U$3") (pin "1") (pinfunction "1_1") (pintype "bidirectional"))
    )
    (net (code "24") (name "Net-(D11-PadA)") (class "Default")
      (node (ref "D11") (pin "A") (pinfunction "A_A") (pintype "passive"))
      (node (ref "U$6") (pin "1") (pinfunction "1_1") (pintype "bidirectional"))
    )
    (net (code "25") (name "Net-(D12-PadA)") (class "Default")
      (node (ref "D12") (pin "A") (pinfunction "A_A") (pintype "passive"))
      (node (ref "U$9") (pin "1") (pinfunction "1_1") (pintype "bidirectional"))
    )
    (net (code "26") (name "Net-(D13-PadA)") (class "Default")
      (node (ref "D13") (pin "A") (pinfunction "A_A") (pintype "passive"))
      (node (ref "U$11") (pin "1") (pinfunction "1_1") (pintype "bidirectional"))
    )
    (net (code "27") (name "Net-(D14-PadA)") (class "Default")
      (node (ref "D14") (pin "A") (pinfunction "A_A") (pintype "passive"))
      (node (ref "U$25") (pin "1") (pinfunction "1_1") (pintype "bidirectional"))
    )
    (net (code "28") (name "Net-(D15-PadA)") (class "Default")
      (node (ref "D15") (pin "A") (pinfunction "A_A") (pintype "passive"))
      (node (ref "U$23") (pin "1") (pinfunction "1_1") (pintype "bidirectional"))
    )
    (net (code "29") (name "Net-(D16-PadA)") (class "Default")
      (node (ref "D16") (pin "A") (pinfunction "A_A") (pintype "passive"))
      (node (ref "U$17") (pin "1") (pinfunction "1_1") (pintype "bidirectional"))
    )
    (net (code "30") (name "Net-(D17-PadA)") (class "Default")
      (node (ref "D17") (pin "A") (pinfunction "A_A") (pintype "passive"))
      (node (ref "U$18") (pin "1") (pinfunction "1_1") (pintype "bidirectional"))
    )
    (net (code "31") (name "Net-(D18-PadA)") (class "Default")
      (node (ref "D18") (pin "A") (pinfunction "A_A") (pintype "passive"))
      (node (ref "U$19") (pin "1") (pinfunction "1_1") (pintype "bidirectional"))
    )
    (net (code "32") (name "Net-(D19-PadA)") (class "Default")
      (node (ref "D19") (pin "A") (pinfunction "A_A") (pintype "passive"))
      (node (ref "U$16") (pin "1") (pinfunction "1_1") (pintype "bidirectional"))
    )
    (net (code "33") (name "Net-(D20-PadA)") (class "Default")
      (node (ref "D20") (pin "A") (pinfunction "A_A") (pintype "passive"))
      (node (ref "U$26") (pin "1") (pinfunction "1_1") (pintype "bidirectional"))
    )
    (net (code "34") (name "Net-(D21-PadA)") (class "Default")
      (node (ref "D21") (pin "A") (pinfunction "A_A") (pintype "passive"))
      (node (ref "U$28") (pin "1") (pinfunction "1_1") (pintype "bidirectional"))
    )
    (net (code "35") (name "Net-(D22-PadA)") (class "Default")
      (node (ref "D22") (pin "A") (pinfunction "A_A") (pintype "passive"))
      (node (ref "U$31") (pin "1") (pinfunction "1_1") (pintype "bidirectional"))
    )
    (net (code "36") (name "Net-(D23-PadA)") (class "Default")
      (node (ref "D23") (pin "A") (pinfunction "A_A") (pintype "passive"))
      (node (ref "U$29") (pin "1") (pinfunction "1_1") (pintype "bidirectional"))
    )
    (net (code "37") (name "Net-(D24-PadA)") (class "Default")
      (node (ref "D24") (pin "A") (pinfunction "A_A") (pintype "passive"))
      (node (ref "U$20") (pin "1") (pinfunction "1_1") (pintype "bidirectional"))
    )
    (net (code "38") (name "Net-(D25-PadA)") (class "Default")
      (node (ref "D25") (pin "A") (pinfunction "A_A") (pintype "passive"))
      (node (ref "U$24") (pin "1") (pinfunction "1_1") (pintype "bidirectional"))
    )
    (net (code "39") (name "Net-(D26-PadA)") (class "Default")
      (node (ref "D26") (pin "A") (pinfunction "A_A") (pintype "passive"))
      (node (ref "U$27") (pin "1") (pinfunction "1_1") (pintype "bidirectional"))
    )
    (net (code "40") (name "Net-(D27-PadA)") (class "Default")
      (node (ref "D27") (pin "A") (pinfunction "A_A") (pintype "passive"))
      (node (ref "U$30") (pin "1") (pinfunction "1_1") (pintype "bidirectional"))
    )
    (net (code "41") (name "Net-(D28-PadA)") (class "Default")
      (node (ref "D28") (pin "A") (pinfunction "A_A") (pintype "passive"))
      (node (ref "U$21") (pin "1") (pinfunction "1_1") (pintype "bidirectional"))
    )
    (net (code "42") (name "Net-(D29-PadA)") (class "Default")
      (node (ref "D29") (pin "A") (pinfunction "A_A") (pintype "passive"))
      (node (ref "U$36") (pin "1") (pinfunction "1_1") (pintype "bidirectional"))
    )
    (net (code "43") (name "Net-(D30-PadA)") (class "Default")
      (node (ref "D30") (pin "A") (pinfunction "A_A") (pintype "passive"))
      (node (ref "U$37") (pin "1") (pinfunction "1_1") (pintype "bidirectional"))
    )
    (net (code "44") (name "Net-(D31-PadA)") (class "Default")
      (node (ref "D31") (pin "A") (pinfunction "A_A") (pintype "passive"))
      (node (ref "U$38") (pin "1") (pinfunction "1_1") (pintype "bidirectional"))
    )
    (net (code "45") (name "Net-(D32-PadA)") (class "Default")
      (node (ref "D32") (pin "A") (pinfunction "A_A") (pintype "passive"))
      (node (ref "U$35") (pin "1") (pinfunction "1_1") (pintype "bidirectional"))
    )
    (net (code "46") (name "Net-(D33-PadA)") (class "Default")
      (node (ref "D33") (pin "A") (pinfunction "A_A") (pintype "passive"))
      (node (ref "U$34") (pin "1") (pinfunction "1_1") (pintype "bidirectional"))
    )
    (net (code "47") (name "Net-(D34-PadA)") (class "Default")
      (node (ref "D34") (pin "A") (pinfunction "A_A") (pintype "passive"))
      (node (ref "U$41") (pin "1") (pinfunction "1_1") (pintype "bidirectional"))
    )
    (net (code "48") (name "Net-(D35-PadA)") (class "Default")
      (node (ref "D35") (pin "A") (pinfunction "A_A") (pintype "passive"))
      (node (ref "U$39") (pin "1") (pinfunction "1_1") (pintype "bidirectional"))
    )
    (net (code "49") (name "Net-(D36-PadA)") (class "Default")
      (node (ref "D36") (pin "A") (pinfunction "A_A") (pintype "passive"))
      (node (ref "U$42") (pin "1") (pinfunction "1_1") (pintype "bidirectional"))
    )
    (net (code "50") (name "Net-(D37-PadA)") (class "Default")
      (node (ref "D37") (pin "A") (pinfunction "A_A") (pintype "passive"))
      (node (ref "U$44") (pin "1") (pinfunction "1_1") (pintype "bidirectional"))
    )
    (net (code "51") (name "Net-(D38-PadA)") (class "Default")
      (node (ref "D38") (pin "A") (pinfunction "A_A") (pintype "passive"))
      (node (ref "U$47") (pin "1") (pinfunction "1_1") (pintype "bidirectional"))
    )
    (net (code "52") (name "Net-(D39-PadA)") (class "Default")
      (node (ref "D39") (pin "A") (pinfunction "A_A") (pintype "passive"))
      (node (ref "U$45") (pin "1") (pinfunction "1_1") (pintype "bidirectional"))
    )
    (net (code "53") (name "Net-(D40-PadA)") (class "Default")
      (node (ref "D40") (pin "A") (pinfunction "A_A") (pintype "passive"))
      (node (ref "U$32") (pin "1") (pinfunction "1_1") (pintype "bidirectional"))
    )
    (net (code "54") (name "Net-(D41-PadA)") (class "Default")
      (node (ref "D41") (pin "A") (pinfunction "A_A") (pintype "passive"))
      (node (ref "U$40") (pin "1") (pinfunction "1_1") (pintype "bidirectional"))
    )
    (net (code "55") (name "Net-(D42-PadA)") (class "Default")
      (node (ref "D42") (pin "A") (pinfunction "A_A") (pintype "passive"))
      (node (ref "U$43") (pin "1") (pinfunction "1_1") (pintype "bidirectional"))
    )
    (net (code "56") (name "Net-(D43-PadA)") (class "Default")
      (node (ref "D43") (pin "A") (pinfunction "A_A") (pintype "passive"))
      (node (ref "U$46") (pin "1") (pinfunction "1_1") (pintype "bidirectional"))
    )
    (net (code "57") (name "Net-(D44-PadA)") (class "Default")
      (node (ref "D44") (pin "A") (pinfunction "A_A") (pintype "passive"))
      (node (ref "U$33") (pin "1") (pinfunction "1_1") (pintype "bidirectional"))
    )
    (net (code "58") (name "Net-(D45-PadA)") (class "Default")
      (node (ref "D45") (pin "A") (pinfunction "A_A") (pintype "passive"))
      (node (ref "U$49") (pin "1") (pinfunction "1_1") (pintype "bidirectional"))
    )
    (net (code "59") (name "Net-(D46-PadA)") (class "Default")
      (node (ref "D46") (pin "A") (pinfunction "A_A") (pintype "passive"))
      (node (ref "U$50") (pin "1") (pinfunction "1_1") (pintype "bidirectional"))
    )
    (net (code "60") (name "Net-(D47-PadA)") (class "Default")
      (node (ref "D47") (pin "A") (pinfunction "A_A") (pintype "passive"))
      (node (ref "U$51") (pin "1") (pinfunction "1_1") (pintype "bidirectional"))
    )
    (net (code "61") (name "Net-(D48-PadA)") (class "Default")
      (node (ref "D48") (pin "A") (pinfunction "A_A") (pintype "passive"))
      (node (ref "U$48") (pin "1") (pinfunction "1_1") (pintype "bidirectional"))
    )
    (net (code "62") (name "Net-(D49-PadA)") (class "Default")
      (node (ref "D49") (pin "A") (pinfunction "A_A") (pintype "passive"))
      (node (ref "U$13") (pin "1") (pinfunction "1_1") (pintype "bidirectional"))
    )
    (net (code "63") (name "Net-(D50-PadA)") (class "Default")
      (node (ref "D50") (pin "A") (pinfunction "A_A") (pintype "passive"))
      (node (ref "U$14") (pin "1") (pinfunction "1_1") (pintype "bidirectional"))
    )
    (net (code "64") (name "Net-(D51-PadA)") (class "Default")
      (node (ref "D51") (pin "A") (pinfunction "A_A") (pintype "passive"))
      (node (ref "U$15") (pin "1") (pinfunction "1_1") (pintype "bidirectional"))
    )
    (net (code "65") (name "Net-(J1-D+)") (class "Default")
      (node (ref "J1") (pin "3") (pinfunction "D+_3") (pintype "bidirectional"))
      (node (ref "R8") (pin "1") (pinfunction "1_1") (pintype "passive"))
    )
    (net (code "66") (name "Net-(J1-D-)") (class "Default")
      (node (ref "J1") (pin "2") (pinfunction "D-_2") (pintype "bidirectional"))
      (node (ref "R7") (pin "1") (pinfunction "1_1") (pintype "passive"))
    )
    (net (code "67") (name "Net-(U1-D+)") (class "Default")
      (node (ref "R8") (pin "2") (pinfunction "2_2") (pintype "passive"))
      (node (ref "U1") (pin "4") (pinfunction "D+_4") (pintype "bidirectional"))
    )
    (net (code "68") (name "Net-(U1-D-)") (class "Default")
      (node (ref "R7") (pin "2") (pinfunction "2_2") (pintype "passive"))
      (node (ref "U1") (pin "3") (pinfunction "D-_3") (pintype "bidirectional"))
    )
    (net (code "69") (name "Net-(U1-PE2(~{HWB}))") (class "Default")
      (node (ref "R6") (pin "2") (pinfunction "2_2") (pintype "passive"))
      (node (ref "U1") (pin "33") (pinfunction "PE2(~{HWB})_33") (pintype "bidirectional"))
    )
    (net (code "70") (name "Net-(U1-XTAL1)") (class "Default")
      (node (ref "C8") (pin "2") (pinfunction "2_2") (pintype "passive"))
      (node (ref "U1") (pin "17") (pinfunction "XTAL1_17") (pintype "input"))
      (node (ref "X1") (pin "3") (pinfunction "3_3") (pintype "passive"))
    )
    (net (code "71") (name "Net-(U1-XTAL2)") (class "Default")
      (node (ref "C7") (pin "2") (pinfunction "2_2") (pintype "passive"))
      (node (ref "U1") (pin "16") (pinfunction "XTAL2_16") (pintype "output"))
      (node (ref "X1") (pin "1") (pinfunction "1_1") (pintype "passive"))
    )
    (net (code "72") (name "Net-(U1-~{RESET})") (class "Default")
      (node (ref "R5") (pin "1") (pinfunction "1_1") (pintype "passive"))
      (node (ref "SW1") (pin "1") (pinfunction "1_1") (pintype "passive"))
      (node (ref "SW1") (pin "2") (pinfunction "2_2") (pintype "passive"))
      (node (ref "U1") (pin "13") (pinfunction "~{RESET}_13") (pintype "input"))
    )
    (net (code "73") (name "ROW0") (class "Default")
      (node (ref "D1") (pin "C") (pinfunction "C_C") (pintype "passive"))
      (node (ref "D14") (pin "C") (pinfunction "C_C") (pintype "passive"))
      (node (ref "D2") (pin "C") (pinfunction "C_C") (pintype "passive"))
      (node (ref "D21") (pin "C") (pinfunction "C_C") (pintype "passive"))
      (node (ref "D22") (pin "C") (pinfunction "C_C") (pintype "passive"))
      (node (ref "D3") (pin "C") (pinfunction "C_C") (pintype "passive"))
      (node (ref "D33") (pin "C") (pinfunction "C_C") (pintype "passive"))
      (node (ref "D34") (pin "C") (pinfunction "C_C") (pintype "passive"))
      (node (ref "D37") (pin "C") (pinfunction "C_C") (pintype "passive"))
      (node (ref "D38") (pin "C") (pinfunction "C_C") (pintype "passive"))
      (node (ref "D6") (pin "C") (pinfunction "C_C") (pintype "passive"))
      (node (ref "D7") (pin "C") (pinfunction "C_C") (pintype "passive"))
      (node (ref "U1") (pin "18") (pinfunction "PD0(OC0B/SCL/INT0)_18") (pintype "bidirectional"))
    )
    (net (code "74") (name "ROW1") (class "Default")
      (node (ref "D15") (pin "C") (pinfunction "C_C") (pintype "passive"))
      (node (ref "D20") (pin "C") (pinfunction "C_C") (pintype "passive"))
      (node (ref "D23") (pin "C") (pinfunction "C_C") (pintype "passive"))
      (node (ref "D24") (pin "C") (pinfunction "C_C") (pintype "passive"))
      (node (ref "D35") (pin "C") (pinfunction "C_C") (pintype "passive"))
      (node (ref "D36") (pin "C") (pinfunction "C_C") (pintype "passive"))
      (node (ref "D39") (pin "C") (pinfunction "C_C") (pintype "passive"))
      (node (ref "D4") (pin "C") (pinfunction "C_C") (pintype "passive"))
      (node (ref "D40") (pin "C") (pinfunction "C_C") (pintype "passive"))
      (node (ref "D5") (pin "C") (pinfunction "C_C") (pintype "passive"))
      (node (ref "D8") (pin "C") (pinfunction "C_C") (pintype "passive"))
      (node (ref "D9") (pin "C") (pinfunction "C_C") (pintype "passive"))
      (node (ref "U1") (pin "22") (pinfunction "PD5(XCK1/~{CTS})_22") (pintype "bidirectional"))
    )
    (net (code "75") (name "ROW2") (class "Default")
      (node (ref "D10") (pin "C") (pinfunction "C_C") (pintype "passive"))
      (node (ref "D11") (pin "C") (pinfunction "C_C") (pintype "passive"))
      (node (ref "D12") (pin "C") (pinfunction "C_C") (pintype "passive"))
      (node (ref "D13") (pin "C") (pinfunction "C_C") (pintype "passive"))
      (node (ref "D25") (pin "C") (pinfunction "C_C") (pintype "passive"))
      (node (ref "D26") (pin "C") (pinfunction "C_C") (pintype "passive"))
      (node (ref "D27") (pin "C") (pinfunction "C_C") (pintype "passive"))
      (node (ref "D28") (pin "C") (pinfunction "C_C") (pintype "passive"))
      (node (ref "D41") (pin "C") (pinfunction "C_C") (pintype "passive"))
      (node (ref "D42") (pin "C") (pinfunction "C_C") (pintype "passive"))
      (node (ref "D43") (pin "C") (pinfunction "C_C") (pintype "passive"))
      (node (ref "D44") (pin "C") (pinfunction "C_C") (pintype "passive"))
      (node (ref "U1") (pin "29") (pinfunction "PB5(PCINT5/OC1A/OC4B/ADC)_29") (pintype "bidirectional"))
    )
    (net (code "76") (name "ROW3") (class "Default")
      (node (ref "D16") (pin "C") (pinfunction "C_C") (pintype "passive"))
      (node (ref "D17") (pin "C") (pinfunction "C_C") (pintype "passive"))
      (node (ref "D18") (pin "C") (pinfunction "C_C") (pintype "passive"))
      (node (ref "D19") (pin "C") (pinfunction "C_C") (pintype "passive"))
      (node (ref "D29") (pin "C") (pinfunction "C_C") (pintype "passive"))
      (node (ref "D30") (pin "C") (pinfunction "C_C") (pintype "passive"))
      (node (ref "D31") (pin "C") (pinfunction "C_C") (pintype "passive"))
      (node (ref "D32") (pin "C") (pinfunction "C_C") (pintype "passive"))
      (node (ref "D45") (pin "C") (pinfunction "C_C") (pintype "passive"))
      (node (ref "D46") (pin "C") (pinfunction "C_C") (pintype "passive"))
      (node (ref "D47") (pin "C") (pinfunction "C_C") (pintype "passive"))
      (node (ref "D48") (pin "C") (pinfunction "C_C") (pintype "passive"))
      (node (ref "D49") (pin "C") (pinfunction "C_C") (pintype "passive"))
      (node (ref "D50") (pin "C") (pinfunction "C_C") (pintype "passive"))
      (node (ref "D51") (pin "C") (pinfunction "C_C") (pintype "passive"))
      (node (ref "U1") (pin "30") (pinfunction "PB6(PCINT6/OC1B/OC4B/ADC)_30") (pintype "bidirectional"))
    )
    (net (code "77") (name "UCAP") (class "Default")
      (node (ref "C6") (pin "2") (pinfunction "2_2") (pintype "passive"))
      (node (ref "U1") (pin "6") (pinfunction "UCAP_6") (pintype "power_in"))
    )
    (net (code "78") (name "VCC") (class "Default")
      (node (ref "C1") (pin "1") (pinfunction "1_1") (pintype "passive"))
      (node (ref "C2") (pin "1") (pinfunction "1_1") (pintype "passive"))
      (node (ref "C3") (pin "1") (pinfunction "1_1") (pintype "passive"))
      (node (ref "C4") (pin "1") (pinfunction "1_1") (pintype "passive"))
      (node (ref "C5") (pin "1") (pinfunction "1_1") (pintype "passive"))
      (node (ref "J1") (pin "1") (pinfunction "VBUS_1") (pintype "power_in"))
      (node (ref "R5") (pin "2") (pinfunction "2_2") (pintype "passive"))
      (node (ref "U1") (pin "14") (pinfunction "VCC_14") (pintype "power_in"))
      (node (ref "U1") (pin "2") (pinfunction "UVCC_2") (pintype "power_in"))
      (node (ref "U1") (pin "24") (pinfunction "AVCC_24") (pintype "power_in"))
      (node (ref "U1") (pin "34") (pinfunction "VCC_34") (pintype "power_in"))
      (node (ref "U1") (pin "44") (pinfunction "AVCC_44") (pintype "power_in"))
      (node (ref "U1") (pin "7") (pinfunction "VBUS_7") (pintype "power_in"))
    )
    (net (code "79") (name "unconnected-(J1-ID-Pad4)") (class "Default")
      (node (ref "J1") (pin "4") (pinfunction "ID_4") (pintype "bidirectional"))
    )
    (net (code "80") (name "unconnected-(U1-AREF-Pad42)") (class "Default")
      (node (ref "U1") (pin "42") (pinfunction "AREF_42") (pintype "input"))
    )
    (net (code "81") (name "unconnected-(U1-PB1(PCINT1{slash}SCLK)-Pad9)") (class "Default")
      (node (ref "U1") (pin "9") (pinfunction "PB1(PCINT1/SCLK)_9") (pintype "bidirectional"))
    )
    (net (code "82") (name "unconnected-(U1-PB2(PDI{slash}PCINT2{slash}MOSI)-Pad10)") (class "Default")
      (node (ref "U1") (pin "10") (pinfunction "PB2(PDI/PCINT2/MOSI)_10") (pintype "bidirectional"))
    )
    (net (code "83") (name "unconnected-(U1-PB3(PDO{slash}PCINT3{slash}MISO)-Pad11)") (class "Default")
      (node (ref "U1") (pin "11") (pinfunction "PB3(PDO/PCINT3/MISO)_11") (pintype "bidirectional"))
    )
    (net (code "84") (name "unconnected-(U1-PB7(PCINT7{slash}OC0A{slash}OC1C{slash}~{RTS})-Pad12)") (class "Default")
      (node (ref "U1") (pin "12") (pinfunction "PB7(PCINT7/OC0A/OC1C/~{RTS})_12") (pintype "bidirectional"))
    )
    (net (code "85") (name "unconnected-(U1-PC6(OC3A{slash}~{OC4A})-Pad31)") (class "Default")
      (node (ref "U1") (pin "31") (pinfunction "PC6(OC3A/~{OC4A})_31") (pintype "bidirectional"))
    )
    (net (code "86") (name "unconnected-(U1-PD1(SDA{slash}INT1)-Pad19)") (class "Default")
      (node (ref "U1") (pin "19") (pinfunction "PD1(SDA/INT1)_19") (pintype "bidirectional"))
    )
    (net (code "87") (name "unconnected-(U1-PD2(RXD1{slash}INT2)-Pad20)") (class "Default")
      (node (ref "U1") (pin "20") (pinfunction "PD2(RXD1/INT2)_20") (pintype "bidirectional"))
    )
    (net (code "88") (name "unconnected-(U1-PD3(TXD1{slash}INT3)-Pad21)") (class "Default")
      (node (ref "U1") (pin "21") (pinfunction "PD3(TXD1/INT3)_21") (pintype "bidirectional"))
    )
    (net (code "89") (name "unconnected-(U1-PE6(INT6{slash}AIN0)-Pad1)") (class "Default")
      (node (ref "U1") (pin "1") (pinfunction "PE6(INT6/AIN0)_1") (pintype "bidirectional"))
    )
  )
)
